# AVRI2CIO_V0_2.net
KiCad netlist of a schematic drawn in EAGLE
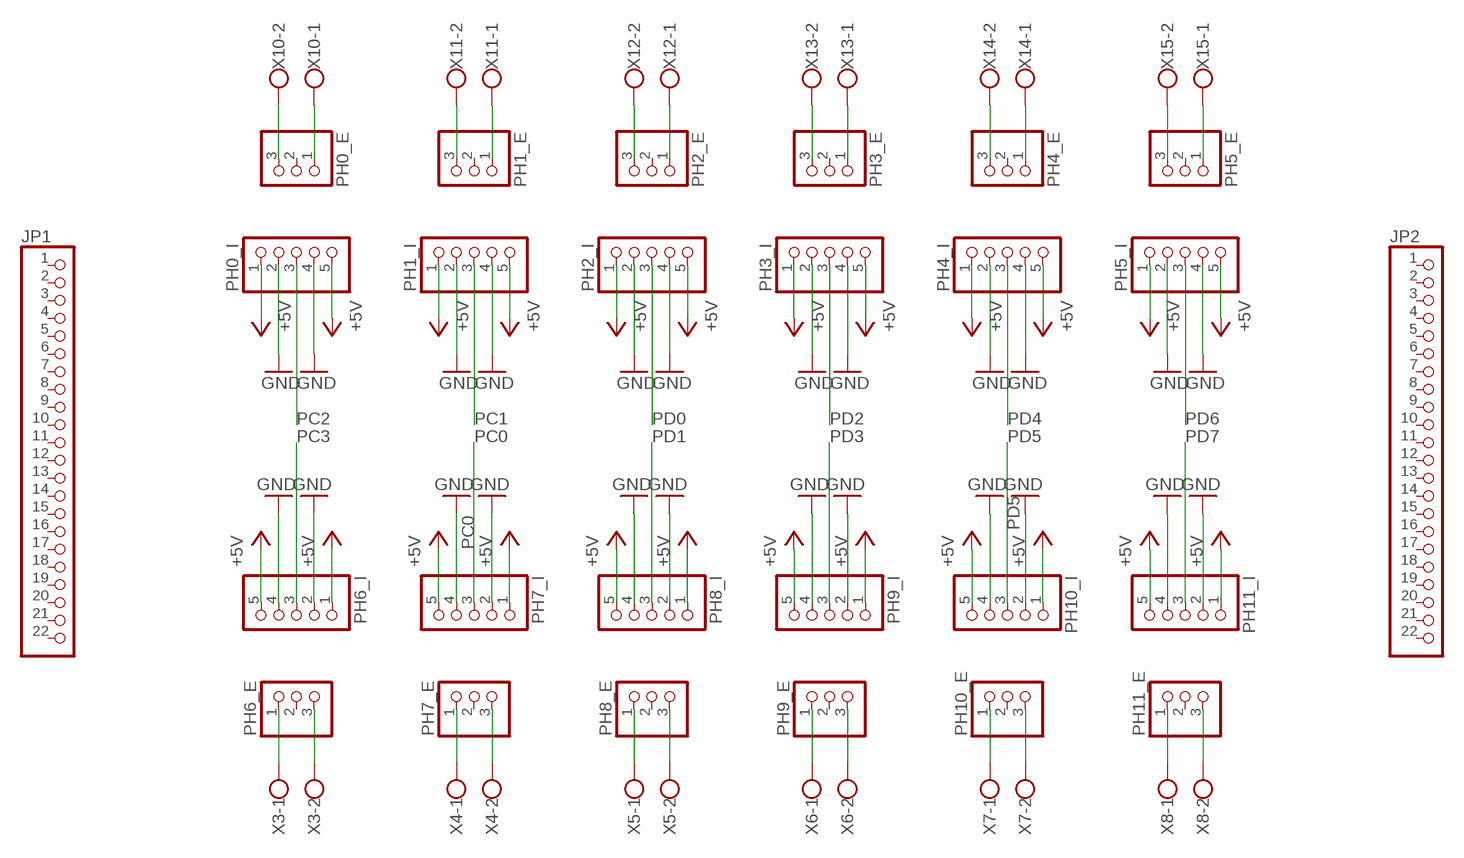
[diagram p0: schematic, sheet 1]

(export (version "E")
  (design (tool "Eeschema 10.0.6"))
  (components
    (comp (ref "JP1")
      (value "PINHD-1X22")
      (footprint "eagle-import:1X22")
      (libsource (lib "eagle-import") (part "PINHD-1X22"))
    )
    (comp (ref "JP2")
      (value "PINHD-1X22")
      (footprint "eagle-import:1X22")
      (libsource (lib "eagle-import") (part "PINHD-1X22"))
    )
    (comp (ref "PH0_E")
      (value "PINHD-1X3")
      (footprint "eagle-import:1X03")
      (libsource (lib "eagle-import") (part "PINHD-1X3"))
    )
    (comp (ref "PH0_I")
      (value "PINHD-1X5")
      (footprint "eagle-import:1X05")
      (libsource (lib "eagle-import") (part "PINHD-1X5"))
    )
    (comp (ref "PH1_E")
      (value "PINHD-1X3")
      (footprint "eagle-import:1X03")
      (libsource (lib "eagle-import") (part "PINHD-1X3"))
    )
    (comp (ref "PH1_I")
      (value "PINHD-1X5")
      (footprint "eagle-import:1X05")
      (libsource (lib "eagle-import") (part "PINHD-1X5"))
    )
    (comp (ref "PH2_E")
      (value "PINHD-1X3")
      (footprint "eagle-import:1X03")
      (libsource (lib "eagle-import") (part "PINHD-1X3"))
    )
    (comp (ref "PH2_I")
      (value "PINHD-1X5")
      (footprint "eagle-import:1X05")
      (libsource (lib "eagle-import") (part "PINHD-1X5"))
    )
    (comp (ref "PH3_E")
      (value "PINHD-1X3")
      (footprint "eagle-import:1X03")
      (libsource (lib "eagle-import") (part "PINHD-1X3"))
    )
    (comp (ref "PH3_I")
      (value "PINHD-1X5")
      (footprint "eagle-import:1X05")
      (libsource (lib "eagle-import") (part "PINHD-1X5"))
    )
    (comp (ref "PH4_E")
      (value "PINHD-1X3")
      (footprint "eagle-import:1X03")
      (libsource (lib "eagle-import") (part "PINHD-1X3"))
    )
    (comp (ref "PH4_I")
      (value "PINHD-1X5")
      (footprint "eagle-import:1X05")
      (libsource (lib "eagle-import") (part "PINHD-1X5"))
    )
    (comp (ref "PH5_E")
      (value "PINHD-1X3")
      (footprint "eagle-import:1X03")
      (libsource (lib "eagle-import") (part "PINHD-1X3"))
    )
    (comp (ref "PH5_I")
      (value "PINHD-1X5")
      (footprint "eagle-import:1X05")
      (libsource (lib "eagle-import") (part "PINHD-1X5"))
    )
    (comp (ref "PH6_E")
      (value "PINHD-1X3")
      (footprint "eagle-import:1X03")
      (libsource (lib "eagle-import") (part "PINHD-1X3"))
    )
    (comp (ref "PH6_I")
      (value "PINHD-1X5")
      (footprint "eagle-import:1X05")
      (libsource (lib "eagle-import") (part "PINHD-1X5"))
    )
    (comp (ref "PH7_E")
      (value "PINHD-1X3")
      (footprint "eagle-import:1X03")
      (libsource (lib "eagle-import") (part "PINHD-1X3"))
    )
    (comp (ref "PH7_I")
      (value "PINHD-1X5")
      (footprint "eagle-import:1X05")
      (libsource (lib "eagle-import") (part "PINHD-1X5"))
    )
    (comp (ref "PH8_E")
      (value "PINHD-1X3")
      (footprint "eagle-import:1X03")
      (libsource (lib "eagle-import") (part "PINHD-1X3"))
    )
    (comp (ref "PH8_I")
      (value "PINHD-1X5")
      (footprint "eagle-import:1X05")
      (libsource (lib "eagle-import") (part "PINHD-1X5"))
    )
    (comp (ref "PH9_E")
      (value "PINHD-1X3")
      (footprint "eagle-import:1X03")
      (libsource (lib "eagle-import") (part "PINHD-1X3"))
    )
    (comp (ref "PH9_I")
      (value "PINHD-1X5")
      (footprint "eagle-import:1X05")
      (libsource (lib "eagle-import") (part "PINHD-1X5"))
    )
    (comp (ref "PH10_E")
      (value "PINHD-1X3")
      (footprint "eagle-import:1X03")
      (libsource (lib "eagle-import") (part "PINHD-1X3"))
    )
    (comp (ref "PH10_I")
      (value "PINHD-1X5")
      (footprint "eagle-import:1X05")
      (libsource (lib "eagle-import") (part "PINHD-1X5"))
    )
    (comp (ref "PH11_E")
      (value "PINHD-1X3")
      (footprint "eagle-import:1X03")
      (libsource (lib "eagle-import") (part "PINHD-1X3"))
    )
    (comp (ref "PH11_I")
      (value "PINHD-1X5")
      (footprint "eagle-import:1X05")
      (libsource (lib "eagle-import") (part "PINHD-1X5"))
    )
    (comp (ref "X3")
      (value "W237-102")
      (footprint "eagle-import:W237-102")
      (fields (field (name "MPN") "237-102"))
      (libsource (lib "eagle-import") (part "W237-102"))
    )
    (comp (ref "X4")
      (value "W237-102")
      (footprint "eagle-import:W237-102")
      (fields (field (name "MPN") "237-102"))
      (libsource (lib "eagle-import") (part "W237-102"))
    )
    (comp (ref "X5")
      (value "W237-102")
      (footprint "eagle-import:W237-102")
      (fields (field (name "MPN") "237-102"))
      (libsource (lib "eagle-import") (part "W237-102"))
    )
    (comp (ref "X6")
      (value "W237-102")
      (footprint "eagle-import:W237-102")
      (fields (field (name "MPN") "237-102"))
      (libsource (lib "eagle-import") (part "W237-102"))
    )
    (comp (ref "X7")
      (value "W237-102")
      (footprint "eagle-import:W237-102")
      (fields (field (name "MPN") "237-102"))
      (libsource (lib "eagle-import") (part "W237-102"))
    )
    (comp (ref "X8")
      (value "W237-102")
      (footprint "eagle-import:W237-102")
      (fields (field (name "MPN") "237-102"))
      (libsource (lib "eagle-import") (part "W237-102"))
    )
    (comp (ref "X10")
      (value "W237-102")
      (footprint "eagle-import:W237-102")
      (fields
        (field (name "MPN") "237-102")
        (field (name "MPN_1") "237-102")
        (field (name "OC_FARNELL") "unknown")
        (field (name "OC_NEWARK") "70K9898")
      )
      (libsource (lib "eagle-import") (part "W237-102"))
    )
    (comp (ref "X11")
      (value "W237-102")
      (footprint "eagle-import:W237-102")
      (fields (field (name "MPN") "237-102"))
      (libsource (lib "eagle-import") (part "W237-102"))
    )
    (comp (ref "X12")
      (value "W237-102")
      (footprint "eagle-import:W237-102")
      (fields (field (name "MPN") "237-102"))
      (libsource (lib "eagle-import") (part "W237-102"))
    )
    (comp (ref "X13")
      (value "W237-102")
      (footprint "eagle-import:W237-102")
      (fields (field (name "MPN") "237-102"))
      (libsource (lib "eagle-import") (part "W237-102"))
    )
    (comp (ref "X14")
      (value "W237-102")
      (footprint "eagle-import:W237-102")
      (fields (field (name "MPN") "237-102"))
      (libsource (lib "eagle-import") (part "W237-102"))
    )
    (comp (ref "X15")
      (value "W237-102")
      (footprint "eagle-import:W237-102")
      (fields (field (name "MPN") "237-102"))
      (libsource (lib "eagle-import") (part "W237-102"))
    )
  )
  (nets
    (net (code "1") (name "+5V") (class "Default")
      (node (ref "PH0_I") (pin "1") (pinfunction "1_1") (pintype "passive"))
      (node (ref "PH0_I") (pin "5") (pinfunction "5_5") (pintype "passive"))
      (node (ref "PH10_I") (pin "1") (pinfunction "1_1") (pintype "passive"))
      (node (ref "PH10_I") (pin "5") (pinfunction "5_5") (pintype "passive"))
      (node (ref "PH11_I") (pin "1") (pinfunction "1_1") (pintype "passive"))
      (node (ref "PH11_I") (pin "5") (pinfunction "5_5") (pintype "passive"))
      (node (ref "PH1_I") (pin "1") (pinfunction "1_1") (pintype "passive"))
      (node (ref "PH1_I") (pin "5") (pinfunction "5_5") (pintype "passive"))
      (node (ref "PH2_I") (pin "1") (pinfunction "1_1") (pintype "passive"))
      (node (ref "PH2_I") (pin "5") (pinfunction "5_5") (pintype "passive"))
      (node (ref "PH3_I") (pin "1") (pinfunction "1_1") (pintype "passive"))
      (node (ref "PH3_I") (pin "5") (pinfunction "5_5") (pintype "passive"))
      (node (ref "PH4_I") (pin "1") (pinfunction "1_1") (pintype "passive"))
      (node (ref "PH4_I") (pin "5") (pinfunction "5_5") (pintype "passive"))
      (node (ref "PH5_I") (pin "1") (pinfunction "1_1") (pintype "passive"))
      (node (ref "PH5_I") (pin "5") (pinfunction "5_5") (pintype "passive"))
      (node (ref "PH6_I") (pin "1") (pinfunction "1_1") (pintype "passive"))
      (node (ref "PH6_I") (pin "5") (pinfunction "5_5") (pintype "passive"))
      (node (ref "PH7_I") (pin "1") (pinfunction "1_1") (pintype "passive"))
      (node (ref "PH7_I") (pin "5") (pinfunction "5_5") (pintype "passive"))
      (node (ref "PH8_I") (pin "1") (pinfunction "1_1") (pintype "passive"))
      (node (ref "PH8_I") (pin "5") (pinfunction "5_5") (pintype "passive"))
      (node (ref "PH9_I") (pin "1") (pinfunction "1_1") (pintype "passive"))
      (node (ref "PH9_I") (pin "5") (pinfunction "5_5") (pintype "passive"))
    )
    (net (code "2") (name "/PC0") (class "Default")
      (node (ref "PH7_I") (pin "3") (pinfunction "3_3") (pintype "passive"))
    )
    (net (code "3") (name "/PC1") (class "Default")
      (node (ref "PH1_I") (pin "3") (pinfunction "3_3") (pintype "passive"))
    )
    (net (code "4") (name "/PC2") (class "Default")
      (node (ref "PH0_I") (pin "3") (pinfunction "3_3") (pintype "passive"))
    )
    (net (code "5") (name "/PC3") (class "Default")
      (node (ref "PH6_I") (pin "3") (pinfunction "3_3") (pintype "passive"))
    )
    (net (code "6") (name "/PD0") (class "Default")
      (node (ref "PH2_I") (pin "3") (pinfunction "3_3") (pintype "passive"))
    )
    (net (code "7") (name "/PD1") (class "Default")
      (node (ref "PH8_I") (pin "3") (pinfunction "3_3") (pintype "passive"))
    )
    (net (code "8") (name "/PD2") (class "Default")
      (node (ref "PH3_I") (pin "3") (pinfunction "3_3") (pintype "passive"))
    )
    (net (code "9") (name "/PD3") (class "Default")
      (node (ref "PH9_I") (pin "3") (pinfunction "3_3") (pintype "passive"))
    )
    (net (code "10") (name "/PD4") (class "Default")
      (node (ref "PH4_I") (pin "3") (pinfunction "3_3") (pintype "passive"))
    )
    (net (code "11") (name "/PD5") (class "Default")
      (node (ref "PH10_I") (pin "3") (pinfunction "3_3") (pintype "passive"))
    )
    (net (code "12") (name "/PD6") (class "Default")
      (node (ref "PH5_I") (pin "3") (pinfunction "3_3") (pintype "passive"))
    )
    (net (code "13") (name "/PD7") (class "Default")
      (node (ref "PH11_I") (pin "3") (pinfunction "3_3") (pintype "passive"))
    )
    (net (code "14") (name "GND") (class "Default")
      (node (ref "PH0_I") (pin "2") (pinfunction "2_2") (pintype "passive"))
      (node (ref "PH0_I") (pin "4") (pinfunction "4_4") (pintype "passive"))
      (node (ref "PH10_I") (pin "2") (pinfunction "2_2") (pintype "passive"))
      (node (ref "PH10_I") (pin "4") (pinfunction "4_4") (pintype "passive"))
      (node (ref "PH11_I") (pin "2") (pinfunction "2_2") (pintype "passive"))
      (node (ref "PH11_I") (pin "4") (pinfunction "4_4") (pintype "passive"))
      (node (ref "PH1_I") (pin "2") (pinfunction "2_2") (pintype "passive"))
      (node (ref "PH1_I") (pin "4") (pinfunction "4_4") (pintype "passive"))
      (node (ref "PH2_I") (pin "2") (pinfunction "2_2") (pintype "passive"))
      (node (ref "PH2_I") (pin "4") (pinfunction "4_4") (pintype "passive"))
      (node (ref "PH3_I") (pin "2") (pinfunction "2_2") (pintype "passive"))
      (node (ref "PH3_I") (pin "4") (pinfunction "4_4") (pintype "passive"))
      (node (ref "PH4_I") (pin "2") (pinfunction "2_2") (pintype "passive"))
      (node (ref "PH4_I") (pin "4") (pinfunction "4_4") (pintype "passive"))
      (node (ref "PH5_I") (pin "2") (pinfunction "2_2") (pintype "passive"))
      (node (ref "PH5_I") (pin "4") (pinfunction "4_4") (pintype "passive"))
      (node (ref "PH6_I") (pin "2") (pinfunction "2_2") (pintype "passive"))
      (node (ref "PH6_I") (pin "4") (pinfunction "4_4") (pintype "passive"))
      (node (ref "PH7_I") (pin "2") (pinfunction "2_2") (pintype "passive"))
      (node (ref "PH7_I") (pin "4") (pinfunction "4_4") (pintype "passive"))
      (node (ref "PH8_I") (pin "2") (pinfunction "2_2") (pintype "passive"))
      (node (ref "PH8_I") (pin "4") (pinfunction "4_4") (pintype "passive"))
      (node (ref "PH9_I") (pin "2") (pinfunction "2_2") (pintype "passive"))
      (node (ref "PH9_I") (pin "4") (pinfunction "4_4") (pintype "passive"))
    )
    (net (code "15") (name "Net-(X3A-KL)") (class "Default")
      (node (ref "PH6_E") (pin "1") (pinfunction "1_1") (pintype "passive"))
      (node (ref "X3") (pin "1") (pinfunction "KL_1") (pintype "passive"))
    )
    (net (code "16") (name "Net-(X3B-KL)") (class "Default")
      (node (ref "PH6_E") (pin "3") (pinfunction "3_3") (pintype "passive"))
      (node (ref "X3") (pin "2") (pinfunction "KL_2") (pintype "passive"))
    )
    (net (code "17") (name "Net-(X4A-KL)") (class "Default")
      (node (ref "PH7_E") (pin "1") (pinfunction "1_1") (pintype "passive"))
      (node (ref "X4") (pin "1") (pinfunction "KL_1") (pintype "passive"))
    )
    (net (code "18") (name "Net-(X4B-KL)") (class "Default")
      (node (ref "PH7_E") (pin "3") (pinfunction "3_3") (pintype "passive"))
      (node (ref "X4") (pin "2") (pinfunction "KL_2") (pintype "passive"))
    )
    (net (code "19") (name "Net-(X5A-KL)") (class "Default")
      (node (ref "PH8_E") (pin "1") (pinfunction "1_1") (pintype "passive"))
      (node (ref "X5") (pin "1") (pinfunction "KL_1") (pintype "passive"))
    )
    (net (code "20") (name "Net-(X5B-KL)") (class "Default")
      (node (ref "PH8_E") (pin "3") (pinfunction "3_3") (pintype "passive"))
      (node (ref "X5") (pin "2") (pinfunction "KL_2") (pintype "passive"))
    )
    (net (code "21") (name "Net-(X6A-KL)") (class "Default")
      (node (ref "PH9_E") (pin "1") (pinfunction "1_1") (pintype "passive"))
      (node (ref "X6") (pin "1") (pinfunction "KL_1") (pintype "passive"))
    )
    (net (code "22") (name "Net-(X6B-KL)") (class "Default")
      (node (ref "PH9_E") (pin "3") (pinfunction "3_3") (pintype "passive"))
      (node (ref "X6") (pin "2") (pinfunction "KL_2") (pintype "passive"))
    )
    (net (code "23") (name "Net-(X7A-KL)") (class "Default")
      (node (ref "PH10_E") (pin "1") (pinfunction "1_1") (pintype "passive"))
      (node (ref "X7") (pin "1") (pinfunction "KL_1") (pintype "passive"))
    )
    (net (code "24") (name "Net-(X7B-KL)") (class "Default")
      (node (ref "PH10_E") (pin "3") (pinfunction "3_3") (pintype "passive"))
      (node (ref "X7") (pin "2") (pinfunction "KL_2") (pintype "passive"))
    )
    (net (code "25") (name "Net-(X8A-KL)") (class "Default")
      (node (ref "PH11_E") (pin "1") (pinfunction "1_1") (pintype "passive"))
      (node (ref "X8") (pin "1") (pinfunction "KL_1") (pintype "passive"))
    )
    (net (code "26") (name "Net-(X8B-KL)") (class "Default")
      (node (ref "PH11_E") (pin "3") (pinfunction "3_3") (pintype "passive"))
      (node (ref "X8") (pin "2") (pinfunction "KL_2") (pintype "passive"))
    )
    (net (code "27") (name "Net-(X10A-KL)") (class "Default")
      (node (ref "PH0_E") (pin "1") (pinfunction "1_1") (pintype "passive"))
      (node (ref "X10") (pin "1") (pinfunction "KL_1") (pintype "passive"))
    )
    (net (code "28") (name "Net-(X10B-KL)") (class "Default")
      (node (ref "PH0_E") (pin "3") (pinfunction "3_3") (pintype "passive"))
      (node (ref "X10") (pin "2") (pinfunction "KL_2") (pintype "passive"))
    )
    (net (code "29") (name "Net-(X11A-KL)") (class "Default")
      (node (ref "PH1_E") (pin "1") (pinfunction "1_1") (pintype "passive"))
      (node (ref "X11") (pin "1") (pinfunction "KL_1") (pintype "passive"))
    )
    (net (code "30") (name "Net-(X11B-KL)") (class "Default")
      (node (ref "PH1_E") (pin "3") (pinfunction "3_3") (pintype "passive"))
      (node (ref "X11") (pin "2") (pinfunction "KL_2") (pintype "passive"))
    )
    (net (code "31") (name "Net-(X12A-KL)") (class "Default")
      (node (ref "PH2_E") (pin "1") (pinfunction "1_1") (pintype "passive"))
      (node (ref "X12") (pin "1") (pinfunction "KL_1") (pintype "passive"))
    )
    (net (code "32") (name "Net-(X12B-KL)") (class "Default")
      (node (ref "PH2_E") (pin "3") (pinfunction "3_3") (pintype "passive"))
      (node (ref "X12") (pin "2") (pinfunction "KL_2") (pintype "passive"))
    )
    (net (code "33") (name "Net-(X13A-KL)") (class "Default")
      (node (ref "PH3_E") (pin "1") (pinfunction "1_1") (pintype "passive"))
      (node (ref "X13") (pin "1") (pinfunction "KL_1") (pintype "passive"))
    )
    (net (code "34") (name "Net-(X13B-KL)") (class "Default")
      (node (ref "PH3_E") (pin "3") (pinfunction "3_3") (pintype "passive"))
      (node (ref "X13") (pin "2") (pinfunction "KL_2") (pintype "passive"))
    )
    (net (code "35") (name "Net-(X14A-KL)") (class "Default")
      (node (ref "PH4_E") (pin "1") (pinfunction "1_1") (pintype "passive"))
      (node (ref "X14") (pin "1") (pinfunction "KL_1") (pintype "passive"))
    )
    (net (code "36") (name "Net-(X14B-KL)") (class "Default")
      (node (ref "PH4_E") (pin "3") (pinfunction "3_3") (pintype "passive"))
      (node (ref "X14") (pin "2") (pinfunction "KL_2") (pintype "passive"))
    )
    (net (code "37") (name "Net-(X15A-KL)") (class "Default")
      (node (ref "PH5_E") (pin "1") (pinfunction "1_1") (pintype "passive"))
      (node (ref "X15") (pin "1") (pinfunction "KL_1") (pintype "passive"))
    )
    (net (code "38") (name "Net-(X15B-KL)") (class "Default")
      (node (ref "PH5_E") (pin "3") (pinfunction "3_3") (pintype "passive"))
      (node (ref "X15") (pin "2") (pinfunction "KL_2") (pintype "passive"))
    )
    (net (code "39") (name "unconnected-(JP1-Pad1)") (class "Default")
      (node (ref "JP1") (pin "1") (pinfunction "1_1") (pintype "passive"))
    )
    (net (code "40") (name "unconnected-(JP1-Pad2)") (class "Default")
      (node (ref "JP1") (pin "2") (pinfunction "2_2") (pintype "passive"))
    )
    (net (code "41") (name "unconnected-(JP1-Pad3)") (class "Default")
      (node (ref "JP1") (pin "3") (pinfunction "3_3") (pintype "passive"))
    )
    (net (code "42") (name "unconnected-(JP1-Pad4)") (class "Default")
      (node (ref "JP1") (pin "4") (pinfunction "4_4") (pintype "passive"))
    )
    (net (code "43") (name "unconnected-(JP1-Pad5)") (class "Default")
      (node (ref "JP1") (pin "5") (pinfunction "5_5") (pintype "passive"))
    )
    (net (code "44") (name "unconnected-(JP1-Pad6)") (class "Default")
      (node (ref "JP1") (pin "6") (pinfunction "6_6") (pintype "passive"))
    )
    (net (code "45") (name "unconnected-(JP1-Pad7)") (class "Default")
      (node (ref "JP1") (pin "7") (pinfunction "7_7") (pintype "passive"))
    )
    (net (code "46") (name "unconnected-(JP1-Pad8)") (class "Default")
      (node (ref "JP1") (pin "8") (pinfunction "8_8") (pintype "passive"))
    )
    (net (code "47") (name "unconnected-(JP1-Pad9)") (class "Default")
      (node (ref "JP1") (pin "9") (pinfunction "9_9") (pintype "passive"))
    )
    (net (code "48") (name "unconnected-(JP1-Pad10)") (class "Default")
      (node (ref "JP1") (pin "10") (pinfunction "10_10") (pintype "passive"))
    )
    (net (code "49") (name "unconnected-(JP1-Pad11)") (class "Default")
      (node (ref "JP1") (pin "11") (pinfunction "11_11") (pintype "passive"))
    )
    (net (code "50") (name "unconnected-(JP1-Pad12)") (class "Default")
      (node (ref "JP1") (pin "12") (pinfunction "12_12") (pintype "passive"))
    )
    (net (code "51") (name "unconnected-(JP1-Pad13)") (class "Default")
      (node (ref "JP1") (pin "13") (pinfunction "13_13") (pintype "passive"))
    )
    (net (code "52") (name "unconnected-(JP1-Pad14)") (class "Default")
      (node (ref "JP1") (pin "14") (pinfunction "14_14") (pintype "passive"))
    )
    (net (code "53") (name "unconnected-(JP1-Pad15)") (class "Default")
      (node (ref "JP1") (pin "15") (pinfunction "15_15") (pintype "passive"))
    )
    (net (code "54") (name "unconnected-(JP1-Pad16)") (class "Default")
      (node (ref "JP1") (pin "16") (pinfunction "16_16") (pintype "passive"))
    )
    (net (code "55") (name "unconnected-(JP1-Pad17)") (class "Default")
      (node (ref "JP1") (pin "17") (pinfunction "17_17") (pintype "passive"))
    )
    (net (code "56") (name "unconnected-(JP1-Pad18)") (class "Default")
      (node (ref "JP1") (pin "18") (pinfunction "18_18") (pintype "passive"))
    )
    (net (code "57") (name "unconnected-(JP1-Pad19)") (class "Default")
      (node (ref "JP1") (pin "19") (pinfunction "19_19") (pintype "passive"))
    )
    (net (code "58") (name "unconnected-(JP1-Pad20)") (class "Default")
      (node (ref "JP1") (pin "20") (pinfunction "20_20") (pintype "passive"))
    )
    (net (code "59") (name "unconnected-(JP1-Pad21)") (class "Default")
      (node (ref "JP1") (pin "21") (pinfunction "21_21") (pintype "passive"))
    )
    (net (code "60") (name "unconnected-(JP1-Pad22)") (class "Default")
      (node (ref "JP1") (pin "22") (pinfunction "22_22") (pintype "passive"))
    )
    (net (code "61") (name "unconnected-(JP2-Pad1)") (class "Default")
      (node (ref "JP2") (pin "1") (pinfunction "1_1") (pintype "passive"))
    )
    (net (code "62") (name "unconnected-(JP2-Pad2)") (class "Default")
      (node (ref "JP2") (pin "2") (pinfunction "2_2") (pintype "passive"))
    )
    (net (code "63") (name "unconnected-(JP2-Pad3)") (class "Default")
      (node (ref "JP2") (pin "3") (pinfunction "3_3") (pintype "passive"))
    )
    (net (code "64") (name "unconnected-(JP2-Pad4)") (class "Default")
      (node (ref "JP2") (pin "4") (pinfunction "4_4") (pintype "passive"))
    )
    (net (code "65") (name "unconnected-(JP2-Pad5)") (class "Default")
      (node (ref "JP2") (pin "5") (pinfunction "5_5") (pintype "passive"))
    )
    (net (code "66") (name "unconnected-(JP2-Pad6)") (class "Default")
      (node (ref "JP2") (pin "6") (pinfunction "6_6") (pintype "passive"))
    )
    (net (code "67") (name "unconnected-(JP2-Pad7)") (class "Default")
      (node (ref "JP2") (pin "7") (pinfunction "7_7") (pintype "passive"))
    )
    (net (code "68") (name "unconnected-(JP2-Pad8)") (class "Default")
      (node (ref "JP2") (pin "8") (pinfunction "8_8") (pintype "passive"))
    )
    (net (code "69") (name "unconnected-(JP2-Pad9)") (class "Default")
      (node (ref "JP2") (pin "9") (pinfunction "9_9") (pintype "passive"))
    )
    (net (code "70") (name "unconnected-(JP2-Pad10)") (class "Default")
      (node (ref "JP2") (pin "10") (pinfunction "10_10") (pintype "passive"))
    )
    (net (code "71") (name "unconnected-(JP2-Pad11)") (class "Default")
      (node (ref "JP2") (pin "11") (pinfunction "11_11") (pintype "passive"))
    )
    (net (code "72") (name "unconnected-(JP2-Pad12)") (class "Default")
      (node (ref "JP2") (pin "12") (pinfunction "12_12") (pintype "passive"))
    )
    (net (code "73") (name "unconnected-(JP2-Pad13)") (class "Default")
      (node (ref "JP2") (pin "13") (pinfunction "13_13") (pintype "passive"))
    )
    (net (code "74") (name "unconnected-(JP2-Pad14)") (class "Default")
      (node (ref "JP2") (pin "14") (pinfunction "14_14") (pintype "passive"))
    )
    (net (code "75") (name "unconnected-(JP2-Pad15)") (class "Default")
      (node (ref "JP2") (pin "15") (pinfunction "15_15") (pintype "passive"))
    )
    (net (code "76") (name "unconnected-(JP2-Pad16)") (class "Default")
      (node (ref "JP2") (pin "16") (pinfunction "16_16") (pintype "passive"))
    )
    (net (code "77") (name "unconnected-(JP2-Pad17)") (class "Default")
      (node (ref "JP2") (pin "17") (pinfunction "17_17") (pintype "passive"))
    )
    (net (code "78") (name "unconnected-(JP2-Pad18)") (class "Default")
      (node (ref "JP2") (pin "18") (pinfunction "18_18") (pintype "passive"))
    )
    (net (code "79") (name "unconnected-(JP2-Pad19)") (class "Default")
      (node (ref "JP2") (pin "19") (pinfunction "19_19") (pintype "passive"))
    )
    (net (code "80") (name "unconnected-(JP2-Pad20)") (class "Default")
      (node (ref "JP2") (pin "20") (pinfunction "20_20") (pintype "passive"))
    )
    (net (code "81") (name "unconnected-(JP2-Pad21)") (class "Default")
      (node (ref "JP2") (pin "21") (pinfunction "21_21") (pintype "passive"))
    )
    (net (code "82") (name "unconnected-(JP2-Pad22)") (class "Default")
      (node (ref "JP2") (pin "22") (pinfunction "22_22") (pintype "passive"))
    )
    (net (code "83") (name "unconnected-(PH0_E-Pad2)") (class "Default")
      (node (ref "PH0_E") (pin "2") (pinfunction "2_2") (pintype "passive"))
    )
    (net (code "84") (name "unconnected-(PH1_E-Pad2)") (class "Default")
      (node (ref "PH1_E") (pin "2") (pinfunction "2_2") (pintype "passive"))
    )
    (net (code "85") (name "unconnected-(PH2_E-Pad2)") (class "Default")
      (node (ref "PH2_E") (pin "2") (pinfunction "2_2") (pintype "passive"))
    )
    (net (code "86") (name "unconnected-(PH3_E-Pad2)") (class "Default")
      (node (ref "PH3_E") (pin "2") (pinfunction "2_2") (pintype "passive"))
    )
    (net (code "87") (name "unconnected-(PH4_E-Pad2)") (class "Default")
      (node (ref "PH4_E") (pin "2") (pinfunction "2_2") (pintype "passive"))
    )
    (net (code "88") (name "unconnected-(PH5_E-Pad2)") (class "Default")
      (node (ref "PH5_E") (pin "2") (pinfunction "2_2") (pintype "passive"))
    )
    (net (code "89") (name "unconnected-(PH6_E-Pad2)") (class "Default")
      (node (ref "PH6_E") (pin "2") (pinfunction "2_2") (pintype "passive"))
    )
    (net (code "90") (name "unconnected-(PH7_E-Pad2)") (class "Default")
      (node (ref "PH7_E") (pin "2") (pinfunction "2_2") (pintype "passive"))
    )
    (net (code "91") (name "unconnected-(PH8_E-Pad2)") (class "Default")
      (node (ref "PH8_E") (pin "2") (pinfunction "2_2") (pintype "passive"))
    )
    (net (code "92") (name "unconnected-(PH9_E-Pad2)") (class "Default")
      (node (ref "PH9_E") (pin "2") (pinfunction "2_2") (pintype "passive"))
    )
    (net (code "93") (name "unconnected-(PH10_E-Pad2)") (class "Default")
      (node (ref "PH10_E") (pin "2") (pinfunction "2_2") (pintype "passive"))
    )
    (net (code "94") (name "unconnected-(PH11_E-Pad2)") (class "Default")
      (node (ref "PH11_E") (pin "2") (pinfunction "2_2") (pintype "passive"))
    )
  )
)
